# 780-00057_rev2_Pg1_SCH_NRES_Crate_Slot_M.net
KiCad netlist of a schematic drawn in Altium Designer
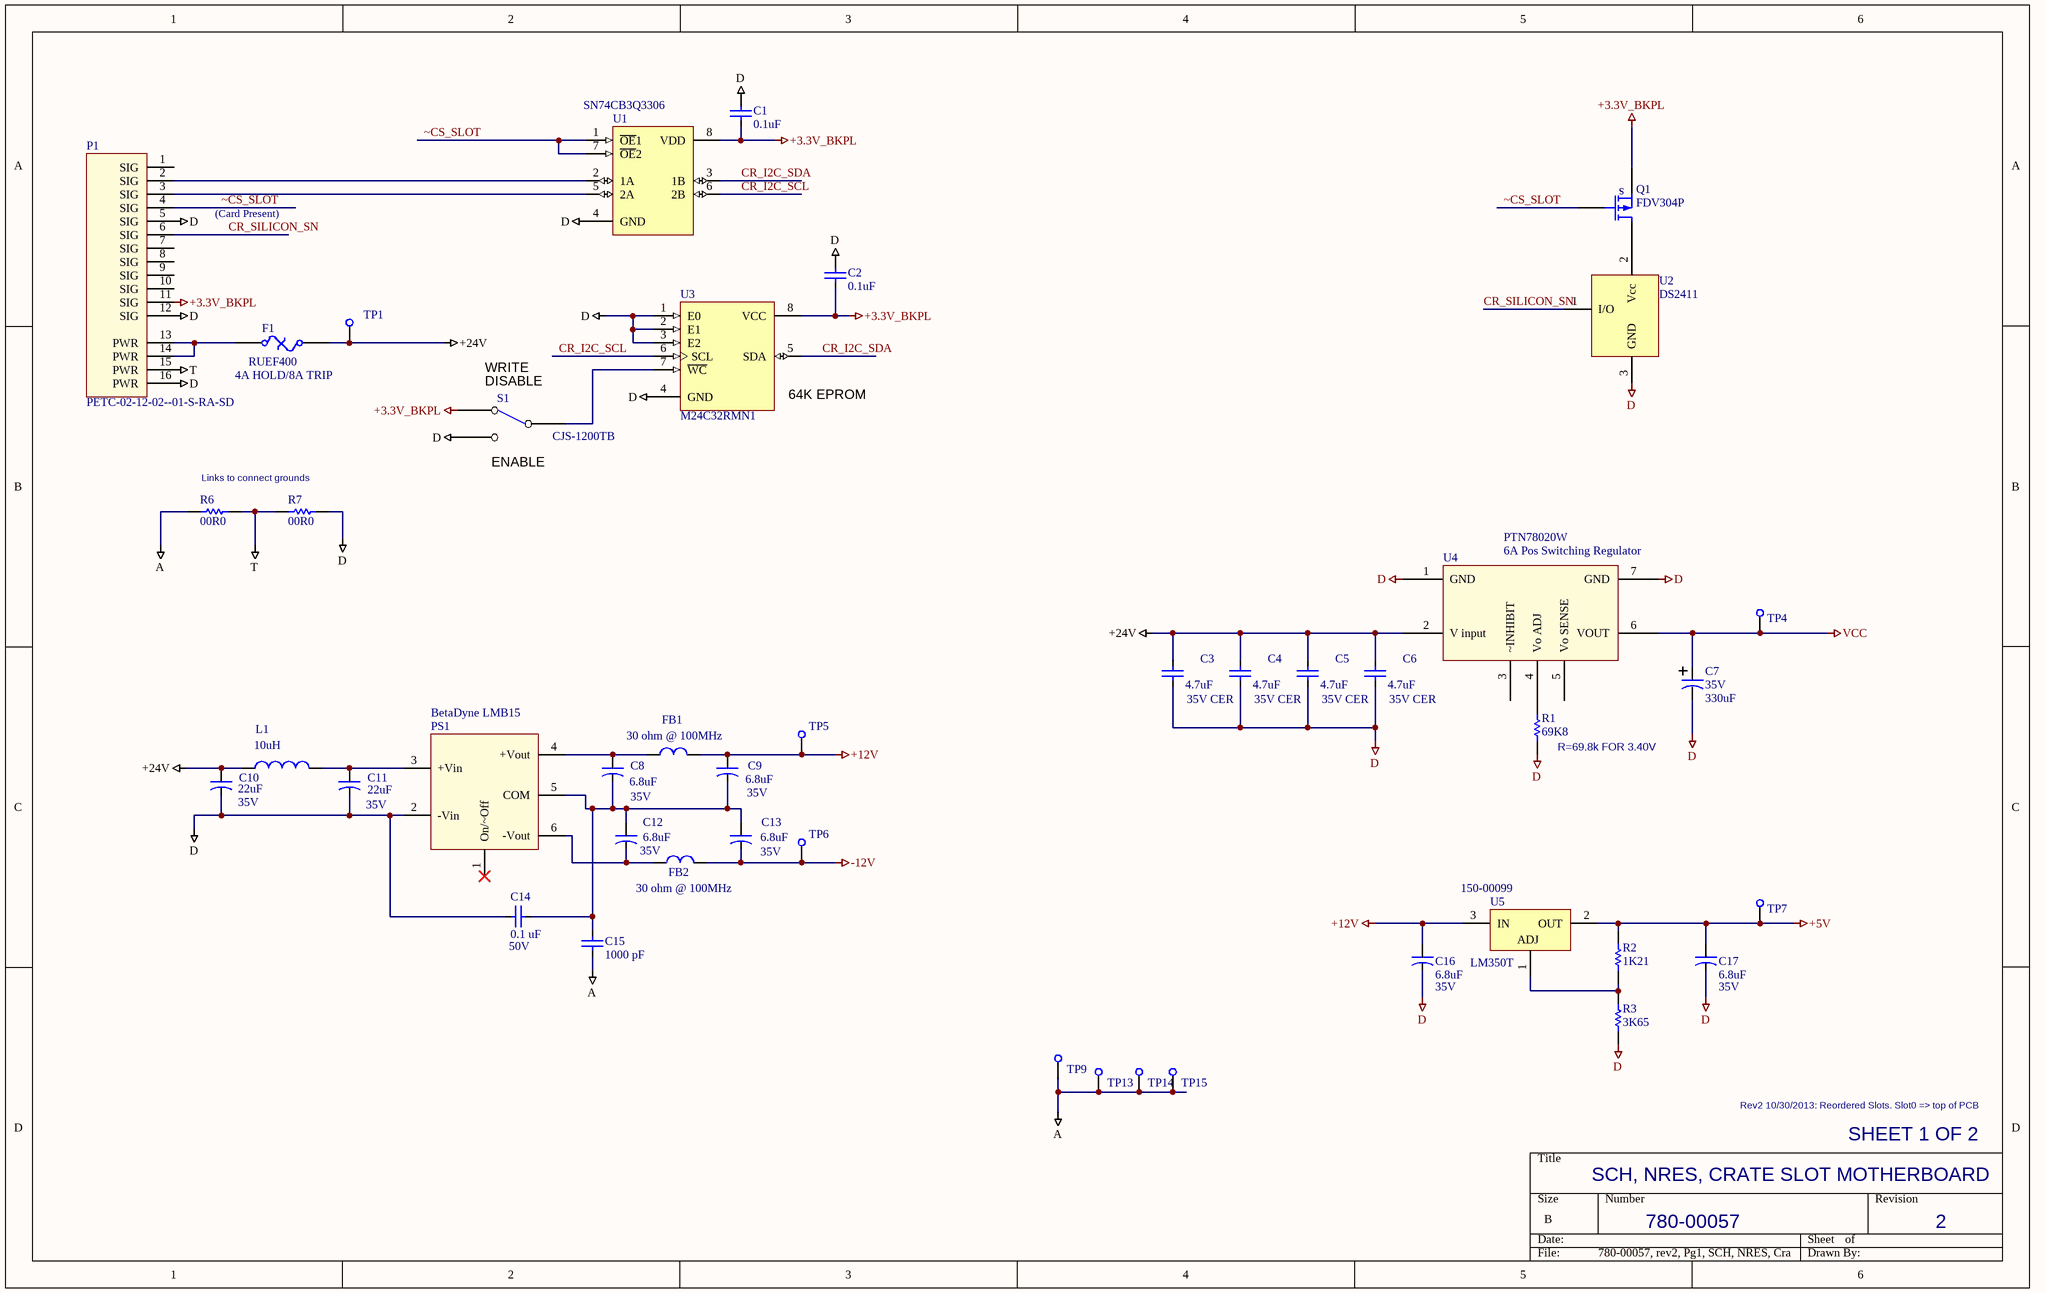
[diagram p0: 780-00057, rev2, Pg1, SCH, NRES, Crate Slot MotherBoard.SchDoc]

(export (version "E")
  (design (tool "Eeschema 10.0.6"))
  (components
    (comp (ref "C1")
      (value "0.1uF")
      (footprint "SMD_0805")
      (description "Capacitor")
      (fields (field (name "MANUFACTURER") "AVX") (field (name "Comment") "Cap SMD"))
      (libsource (lib "Richs Schematic Components") (part "Cap SMD"))
    )
    (comp (ref "C2")
      (value "0.1uF")
      (footprint "SMD_0805")
      (description "Capacitor")
      (fields (field (name "MANUFACTURER") "AVX") (field (name "Comment") "Cap SMD"))
      (libsource (lib "Richs Schematic Components") (part "Cap SMD"))
    )
    (comp (ref "C3")
      (value "35V CER")
      (footprint "SMD_0805")
      (description "Capacitor")
      (fields (field (name "ALTIUM_VALUE") "4.7uF"))
      (libsource (lib "Richs Schematic Components") (part "Cap SMD"))
    )
    (comp (ref "C4")
      (value "35V CER")
      (footprint "SMD_0805")
      (description "Capacitor")
      (fields (field (name "ALTIUM_VALUE") "4.7uF"))
      (libsource (lib "Richs Schematic Components") (part "Cap SMD"))
    )
    (comp (ref "C5")
      (value "35V CER")
      (footprint "SMD_0805")
      (description "Capacitor")
      (fields (field (name "ALTIUM_VALUE") "4.7uF"))
      (libsource (lib "Richs Schematic Components") (part "Cap SMD"))
    )
    (comp (ref "C6")
      (value "35V CER")
      (footprint "SMD_0805")
      (description "Capacitor")
      (fields (field (name "ALTIUM_VALUE") "4.7uF"))
      (libsource (lib "Richs Schematic Components") (part "Cap SMD"))
    )
    (comp (ref "C7")
      (value "35V")
      (footprint "CAP, Thru Hole 10mm dia")
      (description "Radial Thru hole")
      (fields (field (name "ALTIUM_VALUE") "330uF"))
      (libsource (lib "Richs Schematic Components") (part "Cap Elec, 330 uF, 35V"))
    )
    (comp (ref "C8")
      (value "35V")
      (footprint "SMD_CAP_6032")
      (description "outline 6.0mm x 3.2mm")
      (fields (field (name "ALTIUM_VALUE") "6.8uF"))
      (libsource (lib "Richs Schematic Components") (part "Cap Tant 35V"))
    )
    (comp (ref "C9")
      (value "35V")
      (footprint "SMD_CAP_6032")
      (description "outline 6.0mm x 3.2mm")
      (fields (field (name "ALTIUM_VALUE") "6.8uF"))
      (libsource (lib "Richs Schematic Components") (part "Cap Tant 35V"))
    )
    (comp (ref "C10")
      (value "35V")
      (footprint "SMD_CAP_7343")
      (description "outline 6.0mm x 3.2mm")
      (fields (field (name "MANUFACTURER") "Kemet") (field (name "ALTIUM_VALUE") "22uF"))
      (libsource (lib "Richs Schematic Components") (part "Cap Tant 35V"))
    )
    (comp (ref "C11")
      (value "35V")
      (footprint "SMD_CAP_7343")
      (description "outline 6.0mm x 3.2mm")
      (fields (field (name "MANUFACTURER") "Kemet") (field (name "ALTIUM_VALUE") "22uF"))
      (libsource (lib "Richs Schematic Components") (part "Cap Tant 35V"))
    )
    (comp (ref "C12")
      (value "35V")
      (footprint "SMD_CAP_6032")
      (description "outline 6.0mm x 3.2mm")
      (fields (field (name "ALTIUM_VALUE") "6.8uF"))
      (libsource (lib "Richs Schematic Components") (part "Cap Tant 35V"))
    )
    (comp (ref "C13")
      (value "35V")
      (footprint "SMD_CAP_6032")
      (description "outline 6.0mm x 3.2mm")
      (fields (field (name "ALTIUM_VALUE") "6.8uF"))
      (libsource (lib "Richs Schematic Components") (part "Cap Tant 35V"))
    )
    (comp (ref "C14")
      (value "50V")
      (footprint "SMD_0805")
      (description "Capacitor")
      (fields (field (name "ALTIUM_VALUE") "0.1 uF"))
      (libsource (lib "Richs Schematic Components") (part "Cap SMD"))
    )
    (comp (ref "C15")
      (value "1000 pF")
      (footprint "SMD_0805")
      (description "Capacitor")
      (fields (field (name "Comment") "Cap SMD"))
      (libsource (lib "Richs Schematic Components") (part "Cap SMD"))
    )
    (comp (ref "C16")
      (value "35V")
      (footprint "SMD_CAP_6032")
      (description "outline 6.0mm x 3.2mm")
      (fields (field (name "ALTIUM_VALUE") "6.8uF") (field (name "MANUFACTURER") "NICHICON"))
      (libsource (lib "Richs Schematic Components") (part "Cap Tant 35V"))
    )
    (comp (ref "C17")
      (value "35V")
      (footprint "SMD_CAP_6032")
      (description "outline 6.0mm x 3.2mm")
      (fields (field (name "ALTIUM_VALUE") "6.8uF") (field (name "MANUFACTURER") "NICHICON"))
      (libsource (lib "Richs Schematic Components") (part "Cap Tant 35V"))
    )
    (comp (ref "F1")
      (value "RUEF400")
      (footprint "PolySwitch Radial 0.2")
      (description "PolySwitch RUE Series")
      (fields
        (field (name "MANUFACTURER") "Tyco Electronics")
        (field (name "ALTIUM_VALUE") "4A HOLD/8A TRIP")
      )
      (libsource (lib "Richs Schematic Components") (part "Fuse Thermal"))
    )
    (comp (ref "FB1")
      (value "30 ohm @ 100MHz")
      (footprint "SMD_1210_INDUCT")
      (description "Ferrite Bead  SMD 1210")
      (fields (field (name "MANUFACTURER") "Wurth") (field (name "Comment") "Bead"))
      (libsource (lib "Richs Schematic Components") (part "Ferrite Bead SMD 1210"))
    )
    (comp (ref "FB2")
      (value "30 ohm @ 100MHz")
      (footprint "SMD_1210_INDUCT")
      (description "Ferrite Bead  SMD 1210")
      (fields (field (name "MANUFACTURER") "Wurth") (field (name "Comment") "Bead"))
      (libsource (lib "Richs Schematic Components") (part "Ferrite Bead SMD 1210"))
    )
    (comp (ref "L1")
      (value "10uH")
      (footprint "Inductor TDC SLF")
      (description "Inductor")
      (fields (field (name "MANUFACTURER") "TDK") (field (name "Comment") "445-3869-1-ND"))
      (libsource (lib "Richs Schematic Components") (part "Inductor SMD 10uH 1.8A"))
    )
    (comp (ref "P1")
      (value "PETC-02-12-02--01-S-RA-SD")
      (footprint "PETC-02-12-02-01-RA")
      (description "SAMTEC, SIGNAL(12)+PWR(4)")
      (fields (field (name "MANUFACTURER") "SAMTEC"))
      (libsource (lib "Richs Schematic Components") (part "PETC-02-12-02--01-S-RA-SD"))
    )
    (comp (ref "PS1")
      (value "BetaDyne LMB15")
      (footprint "BetaDyne LNB15, DC/DC")
      (description "DC/DC LMB15 15W, Dual Output")
      (libsource (lib "Richs Schematic Components") (part "BetaDyne LMB15"))
    )
    (comp (ref "Q1")
      (value "FDV304P")
      (footprint "SMD_SOT23_3")
      (description "P-MOSFET LOGIC LEVEL")
      (fields (field (name "MANUFACTURER") "Fairchild"))
      (libsource (lib "Richs Schematic Components") (part "FDV304P"))
    )
    (comp (ref "R1")
      (value "69K8")
      (footprint "SMD_0805")
      (description "Resistor 0805")
      (fields (field (name "MANUFACTURER") "Vishay/Dale") (field (name "Comment") "Res 0805"))
      (libsource (lib "Richs Schematic Components") (part "Res SMD"))
    )
    (comp (ref "R2")
      (value "1K21")
      (footprint "SMD_0805")
      (description "Resistor 0805")
      (fields (field (name "MANUFACTURER") "Vishay/Dale") (field (name "Comment") "Res 0805"))
      (libsource (lib "Richs Schematic Components") (part "Res SMD"))
    )
    (comp (ref "R3")
      (value "3K65")
      (footprint "SMD_0805")
      (description "Resistor 0805")
      (fields (field (name "MANUFACTURER") "Vishay/Dale") (field (name "Comment") "Res 0805"))
      (libsource (lib "Richs Schematic Components") (part "Res SMD"))
    )
    (comp (ref "R6")
      (value "00R0")
      (footprint "Protel 99SE BANKS PCB:smd_0805")
      (description "Resistor 0805")
      (fields (field (name "MANUFACTURER") "Vishay/Dale") (field (name "Comment") "Res 0805"))
      (libsource (lib "Richs Schematic Components") (part "Res SMD"))
    )
    (comp (ref "R7")
      (value "00R0")
      (footprint "Protel 99SE BANKS PCB:smd_0805")
      (description "Resistor 0805")
      (fields (field (name "MANUFACTURER") "Vishay/Dale") (field (name "Comment") "Res 0805"))
      (libsource (lib "Richs Schematic Components") (part "Res SMD"))
    )
    (comp (ref "S1")
      (value "CJS-1200TB")
      (footprint "CAS-120B")
      (fields (field (name "MANUFACTURER") "Copal Electronics"))
      (libsource (lib "JON_1_Library") (part "SW_SPDT_DOUG"))
    )
    (comp (ref "TP1")
      (value "Test point")
      (footprint "Protel 99SE BANKS PCB:PAD_80D_052H")
      (description "Test Point")
      (fields (field (name "MANUFACTURER") "Keystone"))
      (libsource (lib "Richs Schematic Components") (part "Test point"))
    )
    (comp (ref "TP4")
      (value "Test point")
      (footprint "Protel 99SE BANKS PCB:PAD_80D_052H")
      (description "Test Point")
      (fields (field (name "MANUFACTURER") "Keystone"))
      (libsource (lib "Richs Schematic Components") (part "Test point"))
    )
    (comp (ref "TP5")
      (value "Test point")
      (footprint "Protel 99SE BANKS PCB:PAD_80D_052H")
      (description "Test Point")
      (fields (field (name "MANUFACTURER") "Keystone"))
      (libsource (lib "Richs Schematic Components") (part "Test point"))
    )
    (comp (ref "TP6")
      (value "Test point")
      (footprint "Protel 99SE BANKS PCB:PAD_80D_052H")
      (description "Test Point")
      (fields (field (name "MANUFACTURER") "Keystone"))
      (libsource (lib "Richs Schematic Components") (part "Test point"))
    )
    (comp (ref "TP7")
      (value "Test point")
      (footprint "Protel 99SE BANKS PCB:PAD_80D_052H")
      (description "Test Point")
      (fields (field (name "MANUFACTURER") "Keystone"))
      (libsource (lib "Richs Schematic Components") (part "Test point"))
    )
    (comp (ref "TP9")
      (value "Test point")
      (footprint "Protel 99SE BANKS PCB:PAD_80D_052H")
      (description "Test Point")
      (fields (field (name "MANUFACTURER") "Keystone"))
      (libsource (lib "Richs Schematic Components") (part "Test point"))
    )
    (comp (ref "TP13")
      (value "Test point")
      (footprint "Protel 99SE BANKS PCB:PAD_80D_052H")
      (description "Test Point")
      (fields (field (name "MANUFACTURER") "Keystone"))
      (libsource (lib "Richs Schematic Components") (part "Test point"))
    )
    (comp (ref "TP14")
      (value "Test point")
      (footprint "Protel 99SE BANKS PCB:PAD_80D_052H")
      (description "Test Point")
      (fields (field (name "MANUFACTURER") "Keystone"))
      (libsource (lib "Richs Schematic Components") (part "Test point"))
    )
    (comp (ref "TP15")
      (value "Test point")
      (footprint "Protel 99SE BANKS PCB:PAD_80D_052H")
      (description "Test Point")
      (fields (field (name "MANUFACTURER") "Keystone"))
      (libsource (lib "Richs Schematic Components") (part "Test point"))
    )
    (comp (ref "U1")
      (value "SN74CB3Q3306")
      (footprint "PW008_N")
      (description "Dual FET Bus Switch")
      (fields (field (name "MANUFACTURER") "TI") (field (name "Comment") "SN74CBT3306PWLE"))
      (libsource (lib "TI Logic Switch") (part "SN74CBT3306PWLE"))
    )
    (comp (ref "U2")
      (value "DS2411")
      (footprint "SMD_SOT23_3")
      (description "Silicon Serial Number")
      (fields (field (name "MANUFACTURER") "MAXIM"))
      (libsource (lib "Richs Schematic Components") (part "DS2411"))
    )
    (comp (ref "U3")
      (value "M24C32RMN1")
      (footprint "SOP8_N")
      (description "32 Kbit Serial I²C Bus EEPROM")
      (libsource (lib "ST Memory EEPROM Serial") (part "M24C32RMN1"))
    )
    (comp (ref "U4")
      (value "6A Pos Switching Regulator")
      (footprint "TEXAS Inst Switching Regulator")
      (description "Pos Adj Switching Regulator")
      (fields (field (name "ALTIUM_VALUE") "PTN78020W"))
      (libsource (lib "Richs Schematic Components") (part "PTN78020W"))
    )
    (comp (ref "U5")
      (value "LM350T")
      (footprint "TO-220AB")
      (description "3-Amp Adjustable Regulator")
      (fields (field (name "MANUFACTURER") "National Semiconductor") (field (name "LCO P/N") "150-00099"))
      (libsource (lib "NSC LDO") (part "LM350T"))
    )
  )
  (nets
    (net (code "1") (name "+3.3V_BKPL") (class "Default")
      (node (ref "C1") (pin "1") (pinfunction "1_1") (pintype "passive"))
      (node (ref "C2") (pin "1") (pinfunction "1_1") (pintype "passive"))
      (node (ref "P1") (pin "11") (pinfunction "SIG_11") (pintype "passive"))
      (node (ref "Q1") (pin "2") (pinfunction "S_2") (pintype "passive"))
      (node (ref "S1") (pin "3") (pinfunction "NC_3") (pintype "passive"))
      (node (ref "U1") (pin "8") (pinfunction "VDD_8") (pintype "power_in"))
      (node (ref "U3") (pin "8") (pinfunction "VCC_8") (pintype "power_in"))
    )
    (net (code "2") (name "+5V") (class "Default")
      (node (ref "C17") (pin "pos") (pinfunction "1_pos") (pintype "passive"))
      (node (ref "R2") (pin "2") (pinfunction "2_2") (pintype "passive"))
      (node (ref "TP7") (pin "1") (pinfunction "TP_1") (pintype "passive"))
      (node (ref "U5") (pin "2") (pinfunction "OUT_2") (pintype "power_in"))
    )
    (net (code "3") (name "+12V") (class "Default")
      (node (ref "C16") (pin "pos") (pinfunction "1_pos") (pintype "passive"))
      (node (ref "C9") (pin "pos") (pinfunction "1_pos") (pintype "passive"))
      (node (ref "FB1") (pin "2") (pinfunction "2_2") (pintype "passive"))
      (node (ref "TP5") (pin "1") (pinfunction "TP_1") (pintype "passive"))
      (node (ref "U5") (pin "3") (pinfunction "IN_3") (pintype "passive"))
    )
    (net (code "4") (name "+24V") (class "Default")
      (node (ref "C10") (pin "pos") (pinfunction "1_pos") (pintype "passive"))
      (node (ref "C3") (pin "2") (pinfunction "2_2") (pintype "passive"))
      (node (ref "C4") (pin "2") (pinfunction "2_2") (pintype "passive"))
      (node (ref "C5") (pin "2") (pinfunction "2_2") (pintype "passive"))
      (node (ref "C6") (pin "2") (pinfunction "2_2") (pintype "passive"))
      (node (ref "F1") (pin "2") (pinfunction "2_2") (pintype "passive"))
      (node (ref "L1") (pin "1") (pinfunction "1_1") (pintype "passive"))
      (node (ref "TP1") (pin "1") (pinfunction "TP_1") (pintype "passive"))
      (node (ref "U4") (pin "2") (pinfunction "V_input_2") (pintype "passive"))
    )
    (net (code "5") (name "-12V") (class "Default")
      (node (ref "C13") (pin "neg") (pinfunction "2_neg") (pintype "passive"))
      (node (ref "FB2") (pin "2") (pinfunction "2_2") (pintype "passive"))
      (node (ref "TP6") (pin "1") (pinfunction "TP_1") (pintype "passive"))
    )
    (net (code "6") (name "/CR_I2C_SCL") (class "Default")
      (node (ref "U1") (pin "6") (pinfunction "2B_6") (pintype "bidirectional"))
      (node (ref "U3") (pin "6") (pinfunction "SCL_6") (pintype "input"))
    )
    (net (code "7") (name "/CR_I2C_SDA") (class "Default")
      (node (ref "U1") (pin "3") (pinfunction "1B_3") (pintype "bidirectional"))
      (node (ref "U3") (pin "5") (pinfunction "SDA_5") (pintype "bidirectional"))
    )
    (net (code "8") (name "/CR_SILICON_SN") (class "Default")
      (node (ref "P1") (pin "6") (pinfunction "SIG_6") (pintype "passive"))
      (node (ref "U2") (pin "1") (pinfunction "I/O_1") (pintype "passive"))
    )
    (net (code "9") (name "/~CS_SLOT") (class "Default")
      (node (ref "P1") (pin "4") (pinfunction "SIG_4") (pintype "passive"))
      (node (ref "Q1") (pin "1") (pinfunction "G_1") (pintype "passive"))
      (node (ref "U1") (pin "1") (pinfunction "~{OE}1_1") (pintype "input"))
      (node (ref "U1") (pin "7") (pinfunction "~{OE}2_7") (pintype "input"))
    )
    (net (code "10") (name "A") (class "Default")
      (node (ref "C15") (pin "1") (pinfunction "1_1") (pintype "passive"))
      (node (ref "R6") (pin "1") (pinfunction "1_1") (pintype "passive"))
      (node (ref "TP13") (pin "1") (pinfunction "TP_1") (pintype "passive"))
      (node (ref "TP14") (pin "1") (pinfunction "TP_1") (pintype "passive"))
      (node (ref "TP15") (pin "1") (pinfunction "TP_1") (pintype "passive"))
      (node (ref "TP9") (pin "1") (pinfunction "TP_1") (pintype "passive"))
    )
    (net (code "11") (name "D") (class "Default")
      (node (ref "C1") (pin "2") (pinfunction "2_2") (pintype "passive"))
      (node (ref "C10") (pin "neg") (pinfunction "2_neg") (pintype "passive"))
      (node (ref "C11") (pin "neg") (pinfunction "2_neg") (pintype "passive"))
      (node (ref "C14") (pin "1") (pinfunction "1_1") (pintype "passive"))
      (node (ref "C16") (pin "neg") (pinfunction "2_neg") (pintype "passive"))
      (node (ref "C17") (pin "neg") (pinfunction "2_neg") (pintype "passive"))
      (node (ref "C2") (pin "2") (pinfunction "2_2") (pintype "passive"))
      (node (ref "C3") (pin "1") (pinfunction "1_1") (pintype "passive"))
      (node (ref "C4") (pin "1") (pinfunction "1_1") (pintype "passive"))
      (node (ref "C5") (pin "1") (pinfunction "1_1") (pintype "passive"))
      (node (ref "C6") (pin "1") (pinfunction "1_1") (pintype "passive"))
      (node (ref "C7") (pin "2") (pinfunction "2_2") (pintype "passive"))
      (node (ref "P1") (pin "12") (pinfunction "SIG_12") (pintype "passive"))
      (node (ref "P1") (pin "16") (pinfunction "PWR_16") (pintype "passive"))
      (node (ref "P1") (pin "5") (pinfunction "SIG_5") (pintype "passive"))
      (node (ref "PS1") (pin "2") (pinfunction "-Vin_2") (pintype "passive"))
      (node (ref "R1") (pin "1") (pinfunction "1_1") (pintype "passive"))
      (node (ref "R3") (pin "1") (pinfunction "1_1") (pintype "passive"))
      (node (ref "R7") (pin "2") (pinfunction "2_2") (pintype "passive"))
      (node (ref "S1") (pin "1") (pinfunction "NO_1") (pintype "passive"))
      (node (ref "U1") (pin "4") (pinfunction "GND_4") (pintype "power_in"))
      (node (ref "U2") (pin "3") (pinfunction "GND_3") (pintype "passive"))
      (node (ref "U3") (pin "1") (pinfunction "E0_1") (pintype "input"))
      (node (ref "U3") (pin "2") (pinfunction "E1_2") (pintype "input"))
      (node (ref "U3") (pin "3") (pinfunction "E2_3") (pintype "input"))
      (node (ref "U3") (pin "4") (pinfunction "GND_4") (pintype "power_in"))
      (node (ref "U4") (pin "1") (pinfunction "GND_1") (pintype "passive"))
      (node (ref "U4") (pin "7") (pinfunction "GND_7") (pintype "passive"))
    )
    (net (code "12") (name "Net-(C8-1)") (class "Default")
      (node (ref "C8") (pin "pos") (pinfunction "1_pos") (pintype "passive"))
      (node (ref "FB1") (pin "1") (pinfunction "1_1") (pintype "passive"))
      (node (ref "PS1") (pin "4") (pinfunction "+Vout_4") (pintype "passive"))
    )
    (net (code "13") (name "Net-(C11-1)") (class "Default")
      (node (ref "C11") (pin "pos") (pinfunction "1_pos") (pintype "passive"))
      (node (ref "L1") (pin "2") (pinfunction "2_2") (pintype "passive"))
      (node (ref "PS1") (pin "3") (pinfunction "+Vin_3") (pintype "passive"))
    )
    (net (code "14") (name "Net-(C12-1)") (class "Default")
      (node (ref "C12") (pin "pos") (pinfunction "1_pos") (pintype "passive"))
      (node (ref "C13") (pin "pos") (pinfunction "1_pos") (pintype "passive"))
      (node (ref "C14") (pin "2") (pinfunction "2_2") (pintype "passive"))
      (node (ref "C15") (pin "2") (pinfunction "2_2") (pintype "passive"))
      (node (ref "C8") (pin "neg") (pinfunction "2_neg") (pintype "passive"))
      (node (ref "C9") (pin "neg") (pinfunction "2_neg") (pintype "passive"))
      (node (ref "PS1") (pin "5") (pinfunction "COM_5") (pintype "passive"))
    )
    (net (code "15") (name "Net-(C12-2)") (class "Default")
      (node (ref "C12") (pin "neg") (pinfunction "2_neg") (pintype "passive"))
      (node (ref "FB2") (pin "1") (pinfunction "1_1") (pintype "passive"))
      (node (ref "PS1") (pin "6") (pinfunction "-Vout_6") (pintype "passive"))
    )
    (net (code "16") (name "Net-(F1-Pad1)") (class "Default")
      (node (ref "F1") (pin "1") (pinfunction "1_1") (pintype "passive"))
      (node (ref "P1") (pin "13") (pinfunction "PWR_13") (pintype "passive"))
      (node (ref "P1") (pin "14") (pinfunction "PWR_14") (pintype "passive"))
    )
    (net (code "17") (name "Net-(Q1-D)") (class "Default")
      (node (ref "Q1") (pin "3") (pinfunction "D_3") (pintype "passive"))
      (node (ref "U2") (pin "2") (pinfunction "Vcc_2") (pintype "passive"))
    )
    (net (code "18") (name "Net-(S1-COM)") (class "Default")
      (node (ref "S1") (pin "2") (pinfunction "COM_2") (pintype "passive"))
      (node (ref "U3") (pin "7") (pinfunction "~{WC}_7") (pintype "input"))
    )
    (net (code "19") (name "Net-(U1-1A)") (class "Default")
      (node (ref "P1") (pin "2") (pinfunction "SIG_2") (pintype "passive"))
      (node (ref "U1") (pin "2") (pinfunction "1A_2") (pintype "bidirectional"))
    )
    (net (code "20") (name "Net-(U1-2A)") (class "Default")
      (node (ref "P1") (pin "3") (pinfunction "SIG_3") (pintype "passive"))
      (node (ref "U1") (pin "5") (pinfunction "2A_5") (pintype "bidirectional"))
    )
    (net (code "21") (name "Net-(U4-Vo_ADJ)") (class "Default")
      (node (ref "R1") (pin "2") (pinfunction "2_2") (pintype "passive"))
      (node (ref "U4") (pin "4") (pinfunction "Vo_ADJ_4") (pintype "passive"))
    )
    (net (code "22") (name "Net-(U5-ADJ)") (class "Default")
      (node (ref "R2") (pin "1") (pinfunction "1_1") (pintype "passive"))
      (node (ref "R3") (pin "2") (pinfunction "2_2") (pintype "passive"))
      (node (ref "U5") (pin "1") (pinfunction "ADJ_1") (pintype "power_in"))
    )
    (net (code "23") (name "T") (class "Default")
      (node (ref "P1") (pin "15") (pinfunction "PWR_15") (pintype "passive"))
      (node (ref "R6") (pin "2") (pinfunction "2_2") (pintype "passive"))
      (node (ref "R7") (pin "1") (pinfunction "1_1") (pintype "passive"))
    )
    (net (code "24") (name "VCC") (class "Default")
      (node (ref "C7") (pin "1") (pinfunction "1_1") (pintype "passive"))
      (node (ref "TP4") (pin "1") (pinfunction "TP_1") (pintype "passive"))
      (node (ref "U4") (pin "6") (pinfunction "VOUT_6") (pintype "passive"))
    )
    (net (code "25") (name "unconnected-(P1-SIG-Pad1)") (class "Default")
      (node (ref "P1") (pin "1") (pinfunction "SIG_1") (pintype "passive"))
    )
    (net (code "26") (name "unconnected-(P1-SIG-Pad7)") (class "Default")
      (node (ref "P1") (pin "7") (pinfunction "SIG_7") (pintype "passive"))
    )
    (net (code "27") (name "unconnected-(P1-SIG-Pad8)") (class "Default")
      (node (ref "P1") (pin "8") (pinfunction "SIG_8") (pintype "passive"))
    )
    (net (code "28") (name "unconnected-(P1-SIG-Pad9)") (class "Default")
      (node (ref "P1") (pin "9") (pinfunction "SIG_9") (pintype "passive"))
    )
    (net (code "29") (name "unconnected-(P1-SIG-Pad10)") (class "Default")
      (node (ref "P1") (pin "10") (pinfunction "SIG_10") (pintype "passive"))
    )
    (net (code "30") (name "unconnected-(PS1-On{slash}~Off-Pad1)") (class "Default")
      (node (ref "PS1") (pin "1") (pinfunction "On/~Off_1") (pintype "passive+no_connect"))
    )
    (net (code "31") (name "unconnected-(U4-Vo_SENSE-Pad5)") (class "Default")
      (node (ref "U4") (pin "5") (pinfunction "Vo_SENSE_5") (pintype "passive"))
    )
    (net (code "32") (name "unconnected-(U4-~INHIBIT-Pad3)") (class "Default")
      (node (ref "U4") (pin "3") (pinfunction "~INHIBIT_3") (pintype "passive"))
    )
  )
)
